# M1502X.net
KiCad netlist of a schematic drawn in EAGLE
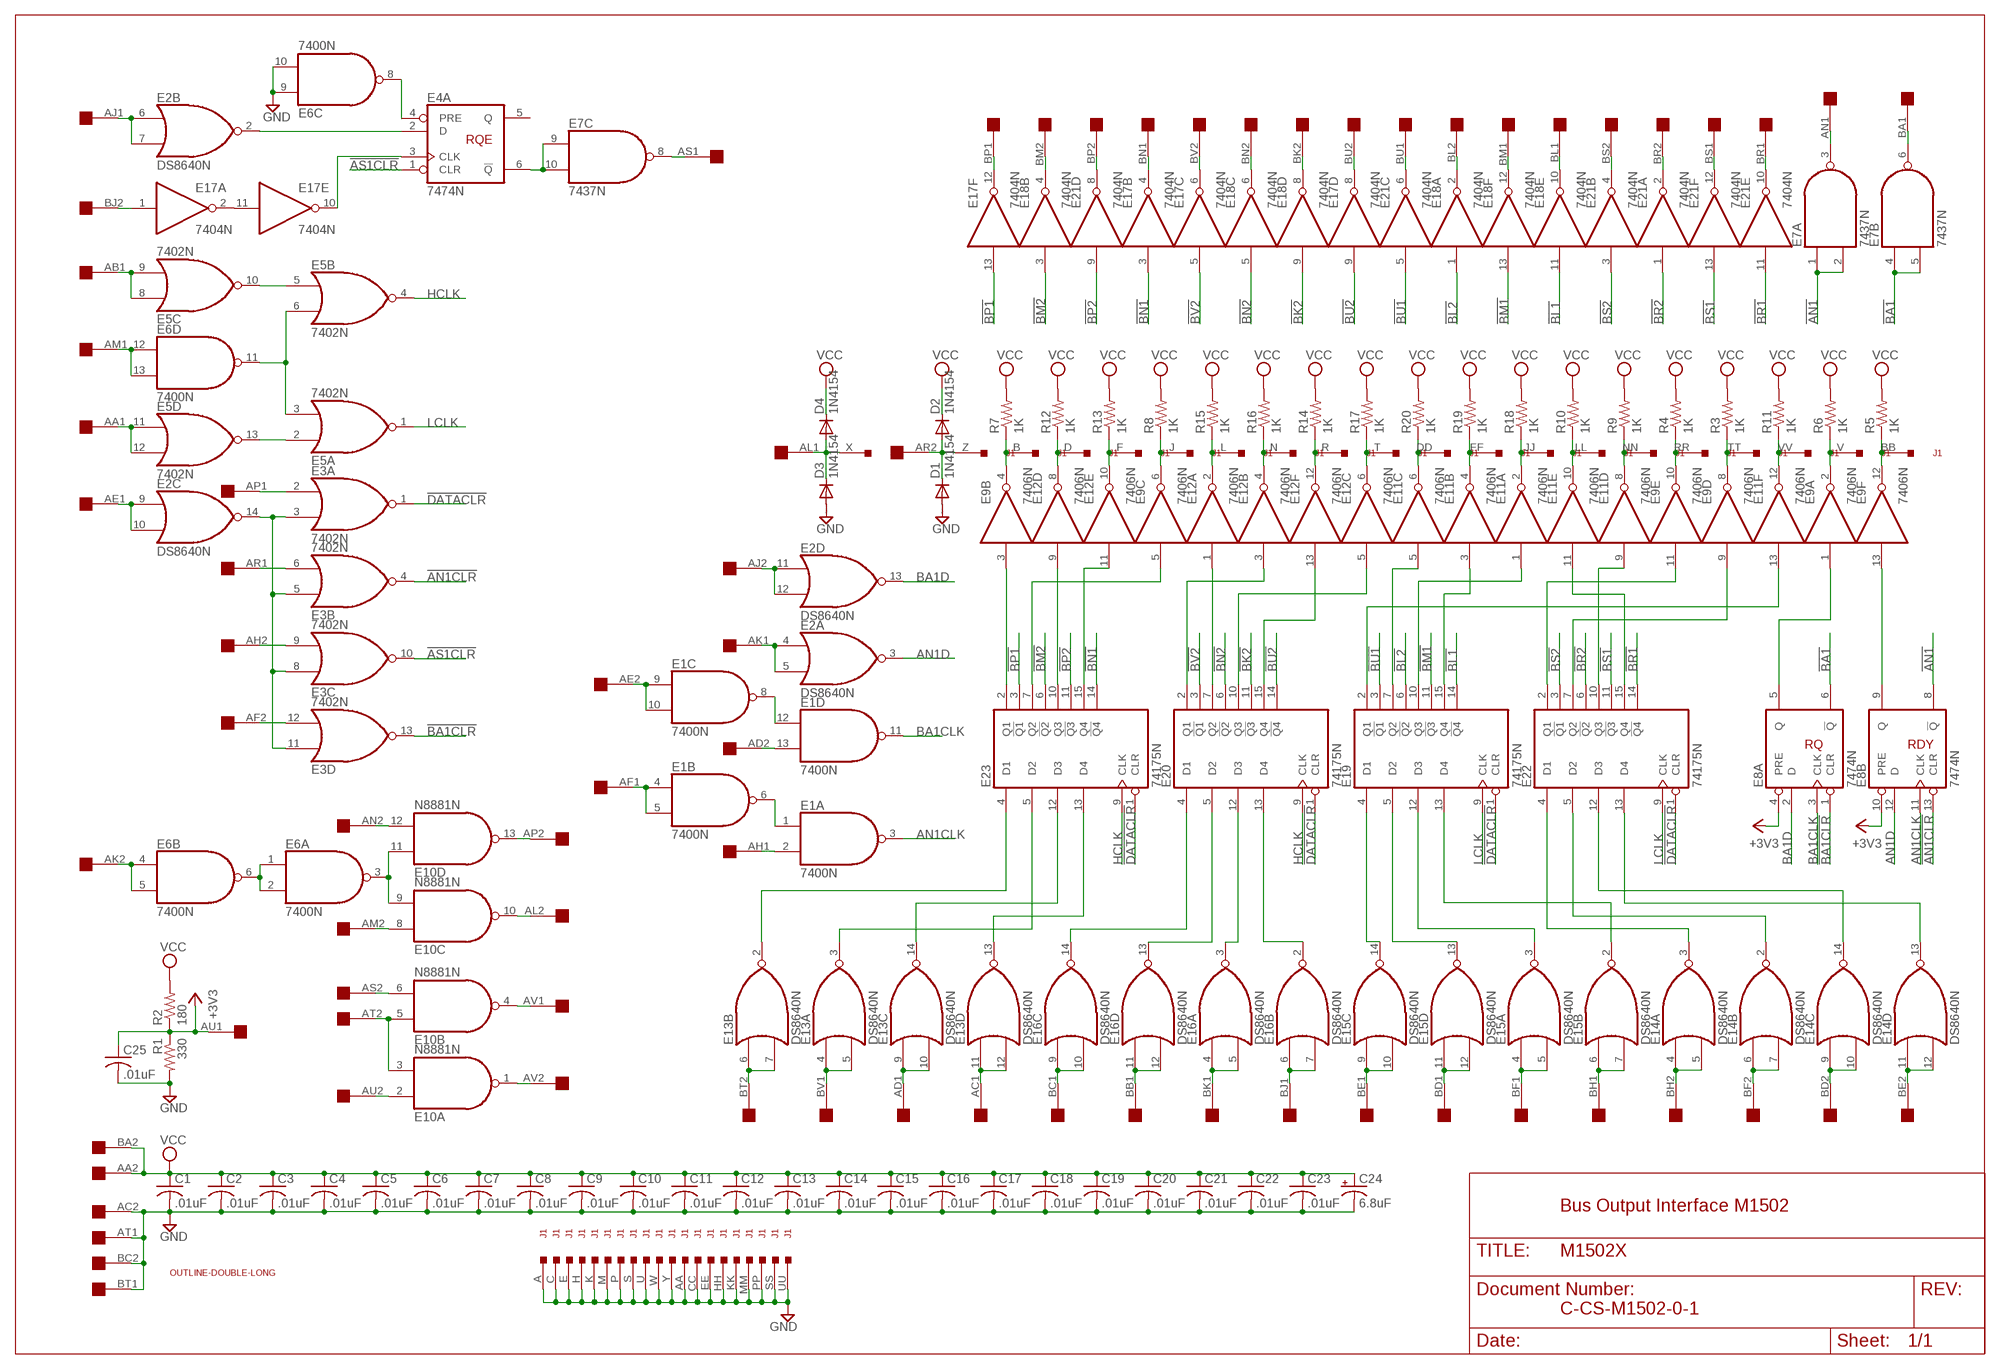
[diagram p0: schematic, sheet 1]

(export (version "E")
  (design (tool "Eeschema 10.0.6"))
  (components
    (comp (ref "C1")
      (value ".01uF")
      (footprint "eagle-import:C075-032X103")
      (libsource (lib "eagle-import") (part "C-US075-032X103"))
    )
    (comp (ref "C2")
      (value ".01uF")
      (footprint "eagle-import:C075-032X103")
      (libsource (lib "eagle-import") (part "C-US075-032X103"))
    )
    (comp (ref "C3")
      (value ".01uF")
      (footprint "eagle-import:C075-032X103")
      (libsource (lib "eagle-import") (part "C-US075-032X103"))
    )
    (comp (ref "C4")
      (value ".01uF")
      (footprint "eagle-import:C075-032X103")
      (libsource (lib "eagle-import") (part "C-US075-032X103"))
    )
    (comp (ref "C5")
      (value ".01uF")
      (footprint "eagle-import:C075-032X103")
      (libsource (lib "eagle-import") (part "C-US075-032X103"))
    )
    (comp (ref "C6")
      (value ".01uF")
      (footprint "eagle-import:C075-032X103")
      (libsource (lib "eagle-import") (part "C-US075-032X103"))
    )
    (comp (ref "C7")
      (value ".01uF")
      (footprint "eagle-import:C075-032X103")
      (libsource (lib "eagle-import") (part "C-US075-032X103"))
    )
    (comp (ref "C8")
      (value ".01uF")
      (footprint "eagle-import:C075-032X103")
      (libsource (lib "eagle-import") (part "C-US075-032X103"))
    )
    (comp (ref "C9")
      (value ".01uF")
      (footprint "eagle-import:C075-032X103")
      (libsource (lib "eagle-import") (part "C-US075-032X103"))
    )
    (comp (ref "C10")
      (value ".01uF")
      (footprint "eagle-import:C075-032X103")
      (libsource (lib "eagle-import") (part "C-US075-032X103"))
    )
    (comp (ref "C11")
      (value ".01uF")
      (footprint "eagle-import:C075-032X103")
      (libsource (lib "eagle-import") (part "C-US075-032X103"))
    )
    (comp (ref "C12")
      (value ".01uF")
      (footprint "eagle-import:C075-032X103")
      (libsource (lib "eagle-import") (part "C-US075-032X103"))
    )
    (comp (ref "C13")
      (value ".01uF")
      (footprint "eagle-import:C075-032X103")
      (libsource (lib "eagle-import") (part "C-US075-032X103"))
    )
    (comp (ref "C14")
      (value ".01uF")
      (footprint "eagle-import:C075-032X103")
      (libsource (lib "eagle-import") (part "C-US075-032X103"))
    )
    (comp (ref "C15")
      (value ".01uF")
      (footprint "eagle-import:C075-032X103")
      (libsource (lib "eagle-import") (part "C-US075-032X103"))
    )
    (comp (ref "C16")
      (value ".01uF")
      (footprint "eagle-import:C075-032X103")
      (libsource (lib "eagle-import") (part "C-US075-032X103"))
    )
    (comp (ref "C17")
      (value ".01uF")
      (footprint "eagle-import:C075-032X103")
      (libsource (lib "eagle-import") (part "C-US075-032X103"))
    )
    (comp (ref "C18")
      (value ".01uF")
      (footprint "eagle-import:C075-032X103")
      (libsource (lib "eagle-import") (part "C-US075-032X103"))
    )
    (comp (ref "C19")
      (value ".01uF")
      (footprint "eagle-import:C075-032X103")
      (libsource (lib "eagle-import") (part "C-US075-032X103"))
    )
    (comp (ref "C20")
      (value ".01uF")
      (footprint "eagle-import:C075-032X103")
      (libsource (lib "eagle-import") (part "C-US075-032X103"))
    )
    (comp (ref "C21")
      (value ".01uF")
      (footprint "eagle-import:C075-032X103")
      (libsource (lib "eagle-import") (part "C-US075-032X103"))
    )
    (comp (ref "C22")
      (value ".01uF")
      (footprint "eagle-import:C075-032X103")
      (libsource (lib "eagle-import") (part "C-US075-032X103"))
    )
    (comp (ref "C23")
      (value ".01uF")
      (footprint "eagle-import:C075-032X103")
      (libsource (lib "eagle-import") (part "C-US075-032X103"))
    )
    (comp (ref "C24")
      (value "6.8uF")
      (footprint "eagle-import:E12-8")
      (libsource (lib "eagle-import") (part "CPOL-USE20-8AXIAL"))
    )
    (comp (ref "C25")
      (value ".01uF")
      (footprint "eagle-import:C075-032X103")
      (libsource (lib "eagle-import") (part "C-US075-032X103"))
    )
    (comp (ref "D1")
      (value "1N4154")
      (footprint "eagle-import:DO35-10")
      (libsource (lib "eagle-import") (part "DIODE-DO35-10"))
    )
    (comp (ref "D2")
      (value "1N4154")
      (footprint "eagle-import:DO35-10")
      (libsource (lib "eagle-import") (part "DIODE-DO35-10"))
    )
    (comp (ref "D3")
      (value "1N4154")
      (footprint "eagle-import:DO35-10")
      (libsource (lib "eagle-import") (part "DIODE-DO35-10"))
    )
    (comp (ref "D4")
      (value "1N4154")
      (footprint "eagle-import:DO35-10")
      (libsource (lib "eagle-import") (part "DIODE-DO35-10"))
    )
    (comp (ref "E1")
      (value "7400N")
      (footprint "eagle-import:DIL14")
      (libsource (lib "eagle-import") (part "7400N"))
    )
    (comp (ref "E2")
      (value "DS8640N")
      (footprint "eagle-import:DIL14")
      (libsource (lib "eagle-import") (part "DS8640N"))
    )
    (comp (ref "E3")
      (value "7402N")
      (footprint "eagle-import:DIL14")
      (libsource (lib "eagle-import") (part "7402N"))
    )
    (comp (ref "E4")
      (value "7474N")
      (footprint "eagle-import:DIL14")
      (libsource (lib "eagle-import") (part "7474NS"))
    )
    (comp (ref "E5")
      (value "7402N")
      (footprint "eagle-import:DIL14")
      (libsource (lib "eagle-import") (part "7402N"))
    )
    (comp (ref "E6")
      (value "7400N")
      (footprint "eagle-import:DIL14")
      (libsource (lib "eagle-import") (part "7400N"))
    )
    (comp (ref "E7")
      (value "7437N")
      (footprint "eagle-import:DIL14")
      (libsource (lib "eagle-import") (part "7437N"))
    )
    (comp (ref "E8")
      (value "7474N")
      (footprint "eagle-import:DIL14")
      (libsource (lib "eagle-import") (part "7474NS"))
    )
    (comp (ref "E9")
      (value "7406N")
      (footprint "eagle-import:DIL14")
      (libsource (lib "eagle-import") (part "7406N"))
    )
    (comp (ref "E10")
      (value "N8881N")
      (footprint "eagle-import:DIL14")
      (libsource (lib "eagle-import") (part "N8881N"))
    )
    (comp (ref "E11")
      (value "7406N")
      (footprint "eagle-import:DIL14")
      (libsource (lib "eagle-import") (part "7406N"))
    )
    (comp (ref "E12")
      (value "7406N")
      (footprint "eagle-import:DIL14")
      (libsource (lib "eagle-import") (part "7406N"))
    )
    (comp (ref "E13")
      (value "DS8640N")
      (footprint "eagle-import:DIL14")
      (libsource (lib "eagle-import") (part "DS8640N"))
    )
    (comp (ref "E14")
      (value "DS8640N")
      (footprint "eagle-import:DIL14")
      (libsource (lib "eagle-import") (part "DS8640N"))
    )
    (comp (ref "E15")
      (value "DS8640N")
      (footprint "eagle-import:DIL14")
      (libsource (lib "eagle-import") (part "DS8640N"))
    )
    (comp (ref "E16")
      (value "DS8640N")
      (footprint "eagle-import:DIL14")
      (libsource (lib "eagle-import") (part "DS8640N"))
    )
    (comp (ref "E17")
      (value "7404N")
      (footprint "eagle-import:DIL14")
      (libsource (lib "eagle-import") (part "7404N"))
    )
    (comp (ref "E18")
      (value "7404N")
      (footprint "eagle-import:DIL14")
      (libsource (lib "eagle-import") (part "7404N"))
    )
    (comp (ref "E19")
      (value "74175N")
      (footprint "eagle-import:DIL16")
      (libsource (lib "eagle-import") (part "74175N"))
    )
    (comp (ref "E20")
      (value "74175N")
      (footprint "eagle-import:DIL16")
      (libsource (lib "eagle-import") (part "74175N"))
    )
    (comp (ref "E21")
      (value "7404N")
      (footprint "eagle-import:DIL14")
      (libsource (lib "eagle-import") (part "7404N"))
    )
    (comp (ref "E22")
      (value "74175N")
      (footprint "eagle-import:DIL16")
      (libsource (lib "eagle-import") (part "74175N"))
    )
    (comp (ref "E23")
      (value "74175N")
      (footprint "eagle-import:DIL16")
      (libsource (lib "eagle-import") (part "74175N"))
    )
    (comp (ref "J1")
      (value "DEC40PINSH")
      (footprint "eagle-import:DEC40PINH")
      (libsource (lib "eagle-import") (part "DEC40PINSH"))
    )
    (comp (ref "R1")
      (value "330")
      (footprint "eagle-import:0207_10")
      (libsource (lib "eagle-import") (part "R-US_0207/10"))
    )
    (comp (ref "R2")
      (value "180")
      (footprint "eagle-import:0207_10")
      (libsource (lib "eagle-import") (part "R-US_0207/10"))
    )
    (comp (ref "R3")
      (value "1K")
      (footprint "eagle-import:0207_10")
      (libsource (lib "eagle-import") (part "R-US_0207/10"))
    )
    (comp (ref "R4")
      (value "1K")
      (footprint "eagle-import:0207_10")
      (libsource (lib "eagle-import") (part "R-US_0207/10"))
    )
    (comp (ref "R5")
      (value "1K")
      (footprint "eagle-import:0207_10")
      (libsource (lib "eagle-import") (part "R-US_0207/10"))
    )
    (comp (ref "R6")
      (value "1K")
      (footprint "eagle-import:0207_10")
      (libsource (lib "eagle-import") (part "R-US_0207/10"))
    )
    (comp (ref "R7")
      (value "1K")
      (footprint "eagle-import:0207_10")
      (libsource (lib "eagle-import") (part "R-US_0207/10"))
    )
    (comp (ref "R8")
      (value "1K")
      (footprint "eagle-import:0207_10")
      (libsource (lib "eagle-import") (part "R-US_0207/10"))
    )
    (comp (ref "R9")
      (value "1K")
      (footprint "eagle-import:0207_10")
      (libsource (lib "eagle-import") (part "R-US_0207/10"))
    )
    (comp (ref "R10")
      (value "1K")
      (footprint "eagle-import:0207_10")
      (libsource (lib "eagle-import") (part "R-US_0207/10"))
    )
    (comp (ref "R11")
      (value "1K")
      (footprint "eagle-import:0207_10")
      (libsource (lib "eagle-import") (part "R-US_0207/10"))
    )
    (comp (ref "R12")
      (value "1K")
      (footprint "eagle-import:0207_10")
      (libsource (lib "eagle-import") (part "R-US_0207/10"))
    )
    (comp (ref "R13")
      (value "1K")
      (footprint "eagle-import:0207_10")
      (libsource (lib "eagle-import") (part "R-US_0207/10"))
    )
    (comp (ref "R14")
      (value "1K")
      (footprint "eagle-import:0207_10")
      (libsource (lib "eagle-import") (part "R-US_0207/10"))
    )
    (comp (ref "R15")
      (value "1K")
      (footprint "eagle-import:0207_10")
      (libsource (lib "eagle-import") (part "R-US_0207/10"))
    )
    (comp (ref "R16")
      (value "1K")
      (footprint "eagle-import:0207_10")
      (libsource (lib "eagle-import") (part "R-US_0207/10"))
    )
    (comp (ref "R17")
      (value "1K")
      (footprint "eagle-import:0207_10")
      (libsource (lib "eagle-import") (part "R-US_0207/10"))
    )
    (comp (ref "R18")
      (value "1K")
      (footprint "eagle-import:0207_10")
      (libsource (lib "eagle-import") (part "R-US_0207/10"))
    )
    (comp (ref "R19")
      (value "1K")
      (footprint "eagle-import:0207_10")
      (libsource (lib "eagle-import") (part "R-US_0207/10"))
    )
    (comp (ref "R20")
      (value "1K")
      (footprint "eagle-import:0207_10")
      (libsource (lib "eagle-import") (part "R-US_0207/10"))
    )
    (comp (ref "U$1")
      (value "OUTLINE-DOUBLE-LONG")
      (footprint "eagle-import:DOUBLE-LONG")
      (libsource (lib "eagle-import") (part "OUTLINE-DOUBLE-LONG"))
    )
    (comp (ref "U$3")
      (value "DOUBLE")
      (footprint "eagle-import:EDGE-CON4")
      (libsource (lib "eagle-import") (part "DOUBLE"))
    )
  )
  (nets
    (net (code "1") (name "+3V3") (class "Default")
      (node (ref "C25") (pin "1") (pinfunction "1_1") (pintype "passive"))
      (node (ref "E8") (pin "10") (pinfunction "PRE_10") (pintype "input"))
      (node (ref "E8") (pin "4") (pinfunction "PRE_4") (pintype "input"))
      (node (ref "R1") (pin "1") (pinfunction "1_1") (pintype "passive"))
      (node (ref "R2") (pin "1") (pinfunction "1_1") (pintype "passive"))
      (node (ref "U$3") (pin "AU1") (pinfunction "1_AU1") (pintype "bidirectional"))
    )
    (net (code "2") (name "/AN1CLK") (class "Default")
      (node (ref "E1") (pin "3") (pinfunction "O_3") (pintype "output"))
      (node (ref "E8") (pin "11") (pinfunction "CLK_11") (pintype "input"))
    )
    (net (code "3") (name "/AN1D") (class "Default")
      (node (ref "E2") (pin "3") (pinfunction "O_3") (pintype "output"))
      (node (ref "E8") (pin "12") (pinfunction "D_12") (pintype "input"))
    )
    (net (code "4") (name "/BA1CLK") (class "Default")
      (node (ref "E1") (pin "11") (pinfunction "O_11") (pintype "output"))
      (node (ref "E8") (pin "3") (pinfunction "CLK_3") (pintype "input"))
    )
    (net (code "5") (name "/BA1D") (class "Default")
      (node (ref "E2") (pin "13") (pinfunction "O_13") (pintype "output"))
      (node (ref "E8") (pin "2") (pinfunction "D_2") (pintype "input"))
    )
    (net (code "6") (name "/HCLK") (class "Default")
      (node (ref "E20") (pin "9") (pinfunction "CLK_9") (pintype "input"))
      (node (ref "E23") (pin "9") (pinfunction "CLK_9") (pintype "input"))
      (node (ref "E5") (pin "4") (pinfunction "O_4") (pintype "output"))
    )
    (net (code "7") (name "/LCLK") (class "Default")
      (node (ref "E19") (pin "9") (pinfunction "CLK_9") (pintype "input"))
      (node (ref "E22") (pin "9") (pinfunction "CLK_9") (pintype "input"))
      (node (ref "E5") (pin "1") (pinfunction "O_1") (pintype "output"))
    )
    (net (code "8") (name "/~{AN1CLR}") (class "Default")
      (node (ref "E3") (pin "4") (pinfunction "O_4") (pintype "output"))
      (node (ref "E8") (pin "13") (pinfunction "CLR_13") (pintype "input"))
    )
    (net (code "9") (name "/~{AN1}") (class "Default")
      (node (ref "E7") (pin "1") (pinfunction "I0_1") (pintype "input"))
      (node (ref "E7") (pin "2") (pinfunction "I1_2") (pintype "input"))
      (node (ref "E8") (pin "8") (pinfunction "~{Q}_8") (pintype "output"))
    )
    (net (code "10") (name "/~{AS1CLR}") (class "Default")
      (node (ref "E3") (pin "10") (pinfunction "O_10") (pintype "output"))
      (node (ref "E4") (pin "1") (pinfunction "CLR_1") (pintype "input"))
    )
    (net (code "11") (name "/~{BA1CLR}") (class "Default")
      (node (ref "E3") (pin "13") (pinfunction "O_13") (pintype "output"))
      (node (ref "E8") (pin "1") (pinfunction "CLR_1") (pintype "input"))
    )
    (net (code "12") (name "/~{BA1}") (class "Default")
      (node (ref "E7") (pin "4") (pinfunction "I0_4") (pintype "input"))
      (node (ref "E7") (pin "5") (pinfunction "I1_5") (pintype "input"))
      (node (ref "E8") (pin "6") (pinfunction "~{Q}_6") (pintype "output"))
    )
    (net (code "13") (name "/~{BK2}") (class "Default")
      (node (ref "E18") (pin "9") (pinfunction "I_9") (pintype "input"))
      (node (ref "E20") (pin "11") (pinfunction "~{Q3}_11") (pintype "output"))
    )
    (net (code "14") (name "/~{BL1}") (class "Default")
      (node (ref "E18") (pin "11") (pinfunction "I_11") (pintype "input"))
      (node (ref "E19") (pin "14") (pinfunction "~{Q4}_14") (pintype "output"))
    )
    (net (code "15") (name "/~{BL2}") (class "Default")
      (node (ref "E18") (pin "1") (pinfunction "I_1") (pintype "input"))
      (node (ref "E19") (pin "6") (pinfunction "~{Q2}_6") (pintype "output"))
    )
    (net (code "16") (name "/~{BM1}") (class "Default")
      (node (ref "E18") (pin "13") (pinfunction "I_13") (pintype "input"))
      (node (ref "E19") (pin "11") (pinfunction "~{Q3}_11") (pintype "output"))
    )
    (net (code "17") (name "/~{BM2}") (class "Default")
      (node (ref "E18") (pin "3") (pinfunction "I_3") (pintype "input"))
      (node (ref "E23") (pin "6") (pinfunction "~{Q2}_6") (pintype "output"))
    )
    (net (code "18") (name "/~{BN1}") (class "Default")
      (node (ref "E17") (pin "3") (pinfunction "I_3") (pintype "input"))
      (node (ref "E23") (pin "14") (pinfunction "~{Q4}_14") (pintype "output"))
    )
    (net (code "19") (name "/~{BN2}") (class "Default")
      (node (ref "E18") (pin "5") (pinfunction "I_5") (pintype "input"))
      (node (ref "E20") (pin "6") (pinfunction "~{Q2}_6") (pintype "output"))
    )
    (net (code "20") (name "/~{BP1}") (class "Default")
      (node (ref "E17") (pin "13") (pinfunction "I_13") (pintype "input"))
      (node (ref "E23") (pin "3") (pinfunction "~{Q1}_3") (pintype "output"))
    )
    (net (code "21") (name "/~{BP2}") (class "Default")
      (node (ref "E21") (pin "9") (pinfunction "I_9") (pintype "input"))
      (node (ref "E23") (pin "11") (pinfunction "~{Q3}_11") (pintype "output"))
    )
    (net (code "22") (name "/~{BR1}") (class "Default")
      (node (ref "E21") (pin "11") (pinfunction "I_11") (pintype "input"))
      (node (ref "E22") (pin "14") (pinfunction "~{Q4}_14") (pintype "output"))
    )
    (net (code "23") (name "/~{BR2}") (class "Default")
      (node (ref "E21") (pin "1") (pinfunction "I_1") (pintype "input"))
      (node (ref "E22") (pin "6") (pinfunction "~{Q2}_6") (pintype "output"))
    )
    (net (code "24") (name "/~{BS1}") (class "Default")
      (node (ref "E21") (pin "13") (pinfunction "I_13") (pintype "input"))
      (node (ref "E22") (pin "11") (pinfunction "~{Q3}_11") (pintype "output"))
    )
    (net (code "25") (name "/~{BS2}") (class "Default")
      (node (ref "E21") (pin "3") (pinfunction "I_3") (pintype "input"))
      (node (ref "E22") (pin "3") (pinfunction "~{Q1}_3") (pintype "output"))
    )
    (net (code "26") (name "/~{BU1}") (class "Default")
      (node (ref "E19") (pin "3") (pinfunction "~{Q1}_3") (pintype "output"))
      (node (ref "E21") (pin "5") (pinfunction "I_5") (pintype "input"))
    )
    (net (code "27") (name "/~{BU2}") (class "Default")
      (node (ref "E17") (pin "9") (pinfunction "I_9") (pintype "input"))
      (node (ref "E20") (pin "14") (pinfunction "~{Q4}_14") (pintype "output"))
    )
    (net (code "28") (name "/~{BV2}") (class "Default")
      (node (ref "E17") (pin "5") (pinfunction "I_5") (pintype "input"))
      (node (ref "E20") (pin "3") (pinfunction "~{Q1}_3") (pintype "output"))
    )
    (net (code "29") (name "/~{DATACLR}") (class "Default")
      (node (ref "E19") (pin "1") (pinfunction "CLR_1") (pintype "input"))
      (node (ref "E20") (pin "1") (pinfunction "CLR_1") (pintype "input"))
      (node (ref "E22") (pin "1") (pinfunction "CLR_1") (pintype "input"))
      (node (ref "E23") (pin "1") (pinfunction "CLR_1") (pintype "input"))
      (node (ref "E3") (pin "1") (pinfunction "O_1") (pintype "output"))
    )
    (net (code "30") (name "GND") (class "Default")
      (node (ref "C1") (pin "2") (pinfunction "2_2") (pintype "passive"))
      (node (ref "C10") (pin "2") (pinfunction "2_2") (pintype "passive"))
      (node (ref "C11") (pin "2") (pinfunction "2_2") (pintype "passive"))
      (node (ref "C12") (pin "2") (pinfunction "2_2") (pintype "passive"))
      (node (ref "C13") (pin "2") (pinfunction "2_2") (pintype "passive"))
      (node (ref "C14") (pin "2") (pinfunction "2_2") (pintype "passive"))
      (node (ref "C15") (pin "2") (pinfunction "2_2") (pintype "passive"))
      (node (ref "C16") (pin "2") (pinfunction "2_2") (pintype "passive"))
      (node (ref "C17") (pin "2") (pinfunction "2_2") (pintype "passive"))
      (node (ref "C18") (pin "2") (pinfunction "2_2") (pintype "passive"))
      (node (ref "C19") (pin "2") (pinfunction "2_2") (pintype "passive"))
      (node (ref "C2") (pin "2") (pinfunction "2_2") (pintype "passive"))
      (node (ref "C20") (pin "2") (pinfunction "2_2") (pintype "passive"))
      (node (ref "C21") (pin "2") (pinfunction "2_2") (pintype "passive"))
      (node (ref "C22") (pin "2") (pinfunction "2_2") (pintype "passive"))
      (node (ref "C23") (pin "2") (pinfunction "2_2") (pintype "passive"))
      (node (ref "C24") (pin "-") (pinfunction "-_-") (pintype "passive"))
      (node (ref "C25") (pin "2") (pinfunction "2_2") (pintype "passive"))
      (node (ref "C3") (pin "2") (pinfunction "2_2") (pintype "passive"))
      (node (ref "C4") (pin "2") (pinfunction "2_2") (pintype "passive"))
      (node (ref "C5") (pin "2") (pinfunction "2_2") (pintype "passive"))
      (node (ref "C6") (pin "2") (pinfunction "2_2") (pintype "passive"))
      (node (ref "C7") (pin "2") (pinfunction "2_2") (pintype "passive"))
      (node (ref "C8") (pin "2") (pinfunction "2_2") (pintype "passive"))
      (node (ref "C9") (pin "2") (pinfunction "2_2") (pintype "passive"))
      (node (ref "D1") (pin "A") (pinfunction "A_A") (pintype "passive"))
      (node (ref "D3") (pin "A") (pinfunction "A_A") (pintype "passive"))
      (node (ref "E6") (pin "10") (pinfunction "I1_10") (pintype "input"))
      (node (ref "E6") (pin "9") (pinfunction "I0_9") (pintype "input"))
      (node (ref "J1") (pin "A") (pinfunction "P$2_A") (pintype "passive"))
      (node (ref "J1") (pin "AA") (pinfunction "P$2_AA") (pintype "passive"))
      (node (ref "J1") (pin "C") (pinfunction "P$2_C") (pintype "passive"))
      (node (ref "J1") (pin "CC") (pinfunction "P$2_CC") (pintype "passive"))
      (node (ref "J1") (pin "E") (pinfunction "P$2_E") (pintype "passive"))
      (node (ref "J1") (pin "EE") (pinfunction "P$2_EE") (pintype "passive"))
      (node (ref "J1") (pin "H") (pinfunction "P$2_H") (pintype "passive"))
      (node (ref "J1") (pin "HH") (pinfunction "P$2_HH") (pintype "passive"))
      (node (ref "J1") (pin "K") (pinfunction "P$2_K") (pintype "passive"))
      (node (ref "J1") (pin "KK") (pinfunction "P$2_KK") (pintype "passive"))
      (node (ref "J1") (pin "M") (pinfunction "P$2_M") (pintype "passive"))
      (node (ref "J1") (pin "MM") (pinfunction "P$2_MM") (pintype "passive"))
      (node (ref "J1") (pin "P") (pinfunction "P$2_P") (pintype "passive"))
      (node (ref "J1") (pin "PP") (pinfunction "P$2_PP") (pintype "passive"))
      (node (ref "J1") (pin "S") (pinfunction "P$2_S") (pintype "passive"))
      (node (ref "J1") (pin "SS") (pinfunction "P$2_SS") (pintype "passive"))
      (node (ref "J1") (pin "U") (pinfunction "P$2_U") (pintype "passive"))
      (node (ref "J1") (pin "UU") (pinfunction "P$2_UU") (pintype "passive"))
      (node (ref "J1") (pin "W") (pinfunction "P$2_W") (pintype "passive"))
      (node (ref "J1") (pin "Y") (pinfunction "P$2_Y") (pintype "passive"))
      (node (ref "R1") (pin "2") (pinfunction "2_2") (pintype "passive"))
      (node (ref "U$3") (pin "AC2") (pinfunction "1_AC2") (pintype "bidirectional"))
      (node (ref "U$3") (pin "AT1") (pinfunction "1_AT1") (pintype "bidirectional"))
      (node (ref "U$3") (pin "BC2") (pinfunction "1_BC2") (pintype "bidirectional"))
      (node (ref "U$3") (pin "BT1") (pinfunction "1_BT1") (pintype "bidirectional"))
    )
    (net (code "31") (name "Net-(E1A-I0)") (class "Default")
      (node (ref "E1") (pin "1") (pinfunction "I0_1") (pintype "input"))
      (node (ref "E1") (pin "6") (pinfunction "O_6") (pintype "output"))
    )
    (net (code "32") (name "Net-(E1A-I1)") (class "Default")
      (node (ref "E1") (pin "2") (pinfunction "I1_2") (pintype "input"))
      (node (ref "U$3") (pin "AH1") (pinfunction "1_AH1") (pintype "bidirectional"))
    )
    (net (code "33") (name "Net-(E1B-I0)") (class "Default")
      (node (ref "E1") (pin "4") (pinfunction "I0_4") (pintype "input"))
      (node (ref "E1") (pin "5") (pinfunction "I1_5") (pintype "input"))
      (node (ref "U$3") (pin "AF1") (pinfunction "1_AF1") (pintype "bidirectional"))
    )
    (net (code "34") (name "Net-(E1C-I0)") (class "Default")
      (node (ref "E1") (pin "10") (pinfunction "I1_10") (pintype "input"))
      (node (ref "E1") (pin "9") (pinfunction "I0_9") (pintype "input"))
      (node (ref "U$3") (pin "AE2") (pinfunction "1_AE2") (pintype "bidirectional"))
    )
    (net (code "35") (name "Net-(E1C-O)") (class "Default")
      (node (ref "E1") (pin "12") (pinfunction "I0_12") (pintype "input"))
      (node (ref "E1") (pin "8") (pinfunction "O_8") (pintype "output"))
    )
    (net (code "36") (name "Net-(E1D-I1)") (class "Default")
      (node (ref "E1") (pin "13") (pinfunction "I1_13") (pintype "input"))
      (node (ref "U$3") (pin "AD2") (pinfunction "1_AD2") (pintype "bidirectional"))
    )
    (net (code "37") (name "Net-(E2A-I0)") (class "Default")
      (node (ref "E2") (pin "4") (pinfunction "I0_4") (pintype "input"))
      (node (ref "E2") (pin "5") (pinfunction "I1_5") (pintype "input"))
      (node (ref "U$3") (pin "AK1") (pinfunction "1_AK1") (pintype "bidirectional"))
    )
    (net (code "38") (name "Net-(E2B-I0)") (class "Default")
      (node (ref "E2") (pin "6") (pinfunction "I0_6") (pintype "input"))
      (node (ref "E2") (pin "7") (pinfunction "I1_7") (pintype "input"))
      (node (ref "U$3") (pin "AJ1") (pinfunction "1_AJ1") (pintype "bidirectional"))
    )
    (net (code "39") (name "Net-(E2B-O)") (class "Default")
      (node (ref "E2") (pin "2") (pinfunction "O_2") (pintype "output"))
      (node (ref "E4") (pin "2") (pinfunction "D_2") (pintype "input"))
    )
    (net (code "40") (name "Net-(E2C-I0)") (class "Default")
      (node (ref "E2") (pin "10") (pinfunction "I1_10") (pintype "input"))
      (node (ref "E2") (pin "9") (pinfunction "I0_9") (pintype "input"))
      (node (ref "U$3") (pin "AE1") (pinfunction "1_AE1") (pintype "bidirectional"))
    )
    (net (code "41") (name "Net-(E2C-O)") (class "Default")
      (node (ref "E2") (pin "14") (pinfunction "O_14") (pintype "output"))
      (node (ref "E3") (pin "11") (pinfunction "I0_11") (pintype "input"))
      (node (ref "E3") (pin "3") (pinfunction "I1_3") (pintype "input"))
      (node (ref "E3") (pin "5") (pinfunction "I0_5") (pintype "input"))
      (node (ref "E3") (pin "8") (pinfunction "I0_8") (pintype "input"))
    )
    (net (code "42") (name "Net-(E2D-I0)") (class "Default")
      (node (ref "E2") (pin "11") (pinfunction "I0_11") (pintype "input"))
      (node (ref "E2") (pin "12") (pinfunction "I1_12") (pintype "input"))
      (node (ref "U$3") (pin "AJ2") (pinfunction "1_AJ2") (pintype "bidirectional"))
    )
    (net (code "43") (name "Net-(E3A-I0)") (class "Default")
      (node (ref "E3") (pin "2") (pinfunction "I0_2") (pintype "input"))
      (node (ref "U$3") (pin "AP1") (pinfunction "1_AP1") (pintype "bidirectional"))
    )
    (net (code "44") (name "Net-(E3B-I1)") (class "Default")
      (node (ref "E3") (pin "6") (pinfunction "I1_6") (pintype "input"))
      (node (ref "U$3") (pin "AR1") (pinfunction "1_AR1") (pintype "bidirectional"))
    )
    (net (code "45") (name "Net-(E3C-I1)") (class "Default")
      (node (ref "E3") (pin "9") (pinfunction "I1_9") (pintype "input"))
      (node (ref "U$3") (pin "AH2") (pinfunction "1_AH2") (pintype "bidirectional"))
    )
    (net (code "46") (name "Net-(E3D-I1)") (class "Default")
      (node (ref "E3") (pin "12") (pinfunction "I1_12") (pintype "input"))
      (node (ref "U$3") (pin "AF2") (pinfunction "1_AF2") (pintype "bidirectional"))
    )
    (net (code "47") (name "Net-(E4A-PRE)") (class "Default")
      (node (ref "E4") (pin "4") (pinfunction "PRE_4") (pintype "input"))
      (node (ref "E6") (pin "8") (pinfunction "O_8") (pintype "output"))
    )
    (net (code "48") (name "Net-(E4A-~{Q})") (class "Default")
      (node (ref "E4") (pin "6") (pinfunction "~{Q}_6") (pintype "output"))
      (node (ref "E7") (pin "10") (pinfunction "I1_10") (pintype "input"))
      (node (ref "E7") (pin "9") (pinfunction "I0_9") (pintype "input"))
    )
    (net (code "49") (name "Net-(E5A-I0)") (class "Default")
      (node (ref "E5") (pin "13") (pinfunction "O_13") (pintype "output"))
      (node (ref "E5") (pin "2") (pinfunction "I0_2") (pintype "input"))
    )
    (net (code "50") (name "Net-(E5A-I1)") (class "Default")
      (node (ref "E5") (pin "3") (pinfunction "I1_3") (pintype "input"))
      (node (ref "E5") (pin "6") (pinfunction "I1_6") (pintype "input"))
      (node (ref "E6") (pin "11") (pinfunction "O_11") (pintype "output"))
    )
    (net (code "51") (name "Net-(E5B-I0)") (class "Default")
      (node (ref "E5") (pin "10") (pinfunction "O_10") (pintype "output"))
      (node (ref "E5") (pin "5") (pinfunction "I0_5") (pintype "input"))
    )
    (net (code "52") (name "Net-(E5C-I0)") (class "Default")
      (node (ref "E5") (pin "8") (pinfunction "I0_8") (pintype "input"))
      (node (ref "E5") (pin "9") (pinfunction "I1_9") (pintype "input"))
      (node (ref "U$3") (pin "AB1") (pinfunction "1_AB1") (pintype "bidirectional"))
    )
    (net (code "53") (name "Net-(E5D-I0)") (class "Default")
      (node (ref "E5") (pin "11") (pinfunction "I0_11") (pintype "input"))
      (node (ref "E5") (pin "12") (pinfunction "I1_12") (pintype "input"))
      (node (ref "U$3") (pin "AA1") (pinfunction "1_AA1") (pintype "bidirectional"))
    )
    (net (code "54") (name "Net-(E6A-I0)") (class "Default")
      (node (ref "E6") (pin "1") (pinfunction "I0_1") (pintype "input"))
      (node (ref "E6") (pin "2") (pinfunction "I1_2") (pintype "input"))
      (node (ref "E6") (pin "6") (pinfunction "O_6") (pintype "output"))
    )
    (net (code "55") (name "Net-(E6B-I0)") (class "Default")
      (node (ref "E6") (pin "4") (pinfunction "I0_4") (pintype "input"))
      (node (ref "E6") (pin "5") (pinfunction "I1_5") (pintype "input"))
      (node (ref "U$3") (pin "AK2") (pinfunction "1_AK2") (pintype "bidirectional"))
    )
    (net (code "56") (name "Net-(E6D-I0)") (class "Default")
      (node (ref "E6") (pin "12") (pinfunction "I0_12") (pintype "input"))
      (node (ref "E6") (pin "13") (pinfunction "I1_13") (pintype "input"))
      (node (ref "U$3") (pin "AM1") (pinfunction "1_AM1") (pintype "bidirectional"))
    )
    (net (code "57") (name "Net-(E7A-O)") (class "Default")
      (node (ref "E7") (pin "3") (pinfunction "O_3") (pintype "output"))
      (node (ref "U$3") (pin "AN1") (pinfunction "1_AN1") (pintype "bidirectional"))
    )
    (net (code "58") (name "Net-(E7B-O)") (class "Default")
      (node (ref "E7") (pin "6") (pinfunction "O_6") (pintype "output"))
      (node (ref "U$3") (pin "BA1") (pinfunction "1_BA1") (pintype "bidirectional"))
    )
    (net (code "59") (name "Net-(E7C-O)") (class "Default")
      (node (ref "E7") (pin "8") (pinfunction "O_8") (pintype "output"))
      (node (ref "U$3") (pin "AS1") (pinfunction "1_AS1") (pintype "bidirectional"))
    )
    (net (code "60") (name "Net-(E8A-Q)") (class "Default")
      (node (ref "E8") (pin "5") (pinfunction "Q_5") (pintype "output"))
      (node (ref "E9") (pin "1") (pinfunction "I_1") (pintype "input"))
    )
    (net (code "61") (name "Net-(E8B-Q)") (class "Default")
      (node (ref "E8") (pin "9") (pinfunction "Q_9") (pintype "output"))
      (node (ref "E9") (pin "13") (pinfunction "I_13") (pintype "input"))
    )
    (net (code "62") (name "Net-(E9A-O)") (class "Default")
      (node (ref "E9") (pin "2") (pinfunction "O_2") (pintype "open_collector"))
      (node (ref "J1") (pin "V") (pinfunction "P$2_V") (pintype "passive"))
      (node (ref "R6") (pin "1") (pinfunction "1_1") (pintype "passive"))
    )
    (net (code "63") (name "Net-(E9B-O)") (class "Default")
      (node (ref "E9") (pin "4") (pinfunction "O_4") (pintype "open_collector"))
      (node (ref "J1") (pin "B") (pinfunction "P$2_B") (pintype "passive"))
      (node (ref "R7") (pin "1") (pinfunction "1_1") (pintype "passive"))
    )
    (net (code "64") (name "Net-(E9C-O)") (class "Default")
      (node (ref "E9") (pin "6") (pinfunction "O_6") (pintype "open_collector"))
      (node (ref "J1") (pin "J") (pinfunction "P$2_J") (pintype "passive"))
      (node (ref "R8") (pin "1") (pinfunction "1_1") (pintype "passive"))
    )
    (net (code "65") (name "Net-(E9D-O)") (class "Default")
      (node (ref "E9") (pin "8") (pinfunction "O_8") (pintype "open_collector"))
      (node (ref "J1") (pin "TT") (pinfunction "P$2_TT") (pintype "passive"))
      (node (ref "R3") (pin "1") (pinfunction "1_1") (pintype "passive"))
    )
    (net (code "66") (name "Net-(E9E-O)") (class "Default")
      (node (ref "E9") (pin "10") (pinfunction "O_10") (pintype "open_collector"))
      (node (ref "J1") (pin "RR") (pinfunction "P$2_RR") (pintype "passive"))
      (node (ref "R4") (pin "1") (pinfunction "1_1") (pintype "passive"))
    )
    (net (code "67") (name "Net-(E9F-O)") (class "Default")
      (node (ref "E9") (pin "12") (pinfunction "O_12") (pintype "open_collector"))
      (node (ref "J1") (pin "BB") (pinfunction "P$2_BB") (pintype "passive"))
      (node (ref "R5") (pin "1") (pinfunction "1_1") (pintype "passive"))
    )
    (net (code "68") (name "Net-(E10A-I0)") (class "Default")
      (node (ref "E10") (pin "2") (pinfunction "I0_2") (pintype "input"))
      (node (ref "U$3") (pin "AU2") (pinfunction "1_AU2") (pintype "bidirectional"))
    )
    (net (code "69") (name "Net-(E10A-I1)") (class "Default")
      (node (ref "E10") (pin "3") (pinfunction "I1_3") (pintype "input"))
      (node (ref "E10") (pin "5") (pinfunction "I0_5") (pintype "input"))
      (node (ref "U$3") (pin "AT2") (pinfunction "1_AT2") (pintype "bidirectional"))
    )
    (net (code "70") (name "Net-(E10A-O)") (class "Default")
      (node (ref "E10") (pin "1") (pinfunction "O_1") (pintype "open_collector"))
      (node (ref "U$3") (pin "AV2") (pinfunction "1_AV2") (pintype "bidirectional"))
    )
    (net (code "71") (name "Net-(E10B-I1)") (class "Default")
      (node (ref "E10") (pin "6") (pinfunction "I1_6") (pintype "input"))
      (node (ref "U$3") (pin "AS2") (pinfunction "1_AS2") (pintype "bidirectional"))
    )
    (net (code "72") (name "Net-(E10B-O)") (class "Default")
      (node (ref "E10") (pin "4") (pinfunction "O_4") (pintype "open_collector"))
      (node (ref "U$3") (pin "AV1") (pinfunction "1_AV1") (pintype "bidirectional"))
    )
    (net (code "73") (name "Net-(E10C-I0)") (class "Default")
      (node (ref "E10") (pin "8") (pinfunction "I0_8") (pintype "input"))
      (node (ref "U$3") (pin "AM2") (pinfunction "1_AM2") (pintype "bidirectional"))
    )
    (net (code "74") (name "Net-(E10C-I1)") (class "Default")
      (node (ref "E10") (pin "11") (pinfunction "I0_11") (pintype "input"))
      (node (ref "E10") (pin "9") (pinfunction "I1_9") (pintype "input"))
      (node (ref "E6") (pin "3") (pinfunction "O_3") (pintype "output"))
    )
    (net (code "75") (name "Net-(E10C-O)") (class "Default")
      (node (ref "E10") (pin "10") (pinfunction "O_10") (pintype "open_collector"))
      (node (ref "U$3") (pin "AL2") (pinfunction "1_AL2") (pintype "bidirectional"))
    )
    (net (code "76") (name "Net-(E10D-I1)") (class "Default")
      (node (ref "E10") (pin "12") (pinfunction "I1_12") (pintype "input"))
      (node (ref "U$3") (pin "AN2") (pinfunction "1_AN2") (pintype "bidirectional"))
    )
    (net (code "77") (name "Net-(E10D-O)") (class "Default")
      (node (ref "E10") (pin "13") (pinfunction "O_13") (pintype "open_collector"))
      (node (ref "U$3") (pin "AP2") (pinfunction "1_AP2") (pintype "bidirectional"))
    )
    (net (code "78") (name "Net-(E11A-I)") (class "Default")
      (node (ref "E11") (pin "1") (pinfunction "I_1") (pintype "input"))
      (node (ref "E19") (pin "10") (pinfunction "Q3_10") (pintype "output"))
    )
    (net (code "79") (name "Net-(E11A-O)") (class "Default")
      (node (ref "E11") (pin "2") (pinfunction "O_2") (pintype "open_collector"))
      (node (ref "J1") (pin "JJ") (pinfunction "P$2_JJ") (pintype "passive"))
      (node (ref "R18") (pin "1") (pinfunction "1_1") (pintype "passive"))
    )
    (net (code "80") (name "Net-(E11B-I)") (class "Default")
      (node (ref "E11") (pin "3") (pinfunction "I_3") (pintype "input"))
      (node (ref "E19") (pin "15") (pinfunction "Q4_15") (pintype "output"))
    )
    (net (code "81") (name "Net-(E11B-O)") (class "Default")
      (node (ref "E11") (pin "4") (pinfunction "O_4") (pintype "open_collector"))
      (node (ref "J1") (pin "FF") (pinfunction "P$2_FF") (pintype "passive"))
      (node (ref "R19") (pin "1") (pinfunction "1_1") (pintype "passive"))
    )
    (net (code "82") (name "Net-(E11C-I)") (class "Default")
      (node (ref "E11") (pin "5") (pinfunction "I_5") (pintype "input"))
      (node (ref "E19") (pin "7") (pinfunction "Q2_7") (pintype "output"))
    )
    (net (code "83") (name "Net-(E11C-O)") (class "Default")
      (node (ref "E11") (pin "6") (pinfunction "O_6") (pintype "open_collector"))
      (node (ref "J1") (pin "DD") (pinfunction "P$2_DD") (pintype "passive"))
      (node (ref "R20") (pin "1") (pinfunction "1_1") (pintype "passive"))
    )
    (net (code "84") (name "Net-(E11D-I)") (class "Default")
      (node (ref "E11") (pin "9") (pinfunction "I_9") (pintype "input"))
      (node (ref "E22") (pin "10") (pinfunction "Q3_10") (pintype "output"))
    )
    (net (code "85") (name "Net-(E11D-O)") (class "Default")
      (node (ref "E11") (pin "8") (pinfunction "O_8") (pintype "open_collector"))
      (node (ref "J1") (pin "NN") (pinfunction "P$2_NN") (pintype "passive"))
      (node (ref "R9") (pin "1") (pinfunction "1_1") (pintype "passive"))
    )
    (net (code "86") (name "Net-(E11E-I)") (class "Default")
      (node (ref "E11") (pin "11") (pinfunction "I_11") (pintype "input"))
      (node (ref "E22") (pin "15") (pinfunction "Q4_15") (pintype "output"))
    )
    (net (code "87") (name "Net-(E11E-O)") (class "Default")
      (node (ref "E11") (pin "10") (pinfunction "O_10") (pintype "open_collector"))
      (node (ref "J1") (pin "LL") (pinfunction "P$2_LL") (pintype "passive"))
      (node (ref "R10") (pin "1") (pinfunction "1_1") (pintype "passive"))
    )
    (net (code "88") (name "Net-(E11F-I)") (class "Default")
      (node (ref "E11") (pin "13") (pinfunction "I_13") (pintype "input"))
      (node (ref "E19") (pin "2") (pinfunction "Q1_2") (pintype "output"))
    )
    (net (code "89") (name "Net-(E11F-O)") (class "Default")
      (node (ref "E11") (pin "12") (pinfunction "O_12") (pintype "open_collector"))
      (node (ref "J1") (pin "VV") (pinfunction "P$2_VV") (pintype "passive"))
      (node (ref "R11") (pin "1") (pinfunction "1_1") (pintype "passive"))
    )
    (net (code "90") (name "Net-(E12A-I)") (class "Default")
      (node (ref "E12") (pin "1") (pinfunction "I_1") (pintype "input"))
      (node (ref "E20") (pin "7") (pinfunction "Q2_7") (pintype "output"))
    )
    (net (code "91") (name "Net-(E12A-O)") (class "Default")
      (node (ref "E12") (pin "2") (pinfunction "O_2") (pintype "open_collector"))
      (node (ref "J1") (pin "L") (pinfunction "P$2_L") (pintype "passive"))
      (node (ref "R15") (pin "1") (pinfunction "1_1") (pintype "passive"))
    )
    (net (code "92") (name "Net-(E12B-I)") (class "Default")
      (node (ref "E12") (pin "3") (pinfunction "I_3") (pintype "input"))
      (node (ref "E20") (pin "2") (pinfunction "Q1_2") (pintype "output"))
    )
    (net (code "93") (name "Net-(E12B-O)") (class "Default")
      (node (ref "E12") (pin "4") (pinfunction "O_4") (pintype "open_collector"))
      (node (ref "J1") (pin "N") (pinfunction "P$2_N") (pintype "passive"))
      (node (ref "R16") (pin "1") (pinfunction "1_1") (pintype "passive"))
    )
    (net (code "94") (name "Net-(E12C-I)") (class "Default")
      (node (ref "E12") (pin "5") (pinfunction "I_5") (pintype "input"))
      (node (ref "E20") (pin "10") (pinfunction "Q3_10") (pintype "output"))
    )
    (net (code "95") (name "Net-(E12C-O)") (class "Default")
      (node (ref "E12") (pin "6") (pinfunction "O_6") (pintype "open_collector"))
      (node (ref "J1") (pin "T") (pinfunction "P$2_T") (pintype "passive"))
      (node (ref "R17") (pin "1") (pinfunction "1_1") (pintype "passive"))
    )
    (net (code "96") (name "Net-(E12D-I)") (class "Default")
      (node (ref "E12") (pin "9") (pinfunction "I_9") (pintype "input"))
      (node (ref "E23") (pin "10") (pinfunction "Q3_10") (pintype "output"))
    )
    (net (code "97") (name "Net-(E12D-O)") (class "Default")
      (node (ref "E12") (pin "8") (pinfunction "O_8") (pintype "open_collector"))
      (node (ref "J1") (pin "D") (pinfunction "P$2_D") (pintype "passive"))
      (node (ref "R12") (pin "1") (pinfunction "1_1") (pintype "passive"))
    )
    (net (code "98") (name "Net-(E12E-I)") (class "Default")
      (node (ref "E12") (pin "11") (pinfunction "I_11") (pintype "input"))
      (node (ref "E23") (pin "15") (pinfunction "Q4_15") (pintype "output"))
    )
    (net (code "99") (name "Net-(E12E-O)") (class "Default")
      (node (ref "E12") (pin "10") (pinfunction "O_10") (pintype "open_collector"))
      (node (ref "J1") (pin "F") (pinfunction "P$2_F") (pintype "passive"))
      (node (ref "R13") (pin "1") (pinfunction "1_1") (pintype "passive"))
    )
    (net (code "100") (name "Net-(E12F-I)") (class "Default")
      (node (ref "E12") (pin "13") (pinfunction "I_13") (pintype "input"))
      (node (ref "E20") (pin "15") (pinfunction "Q4_15") (pintype "output"))
    )
    (net (code "101") (name "Net-(E12F-O)") (class "Default")
      (node (ref "E12") (pin "12") (pinfunction "O_12") (pintype "open_collector"))
      (node (ref "J1") (pin "R") (pinfunction "P$2_R") (pintype "passive"))
      (node (ref "R14") (pin "1") (pinfunction "1_1") (pintype "passive"))
    )
    (net (code "102") (name "Net-(E13A-I0)") (class "Default")
      (node (ref "E13") (pin "4") (pinfunction "I0_4") (pintype "input"))
      (node (ref "E13") (pin "5") (pinfunction "I1_5") (pintype "input"))
      (node (ref "U$3") (pin "BV1") (pinfunction "1_BV1") (pintype "bidirectional"))
    )
    (net (code "103") (name "Net-(E13A-O)") (class "Default")
      (node (ref "E13") (pin "3") (pinfunction "O_3") (pintype "output"))
      (node (ref "E23") (pin "5") (pinfunction "D2_5") (pintype "input"))
    )
    (net (code "104") (name "Net-(E13B-I0)") (class "Default")
      (node (ref "E13") (pin "6") (pinfunction "I0_6") (pintype "input"))
      (node (ref "E13") (pin "7") (pinfunction "I1_7") (pintype "input"))
      (node (ref "U$3") (pin "BT2") (pinfunction "1_BT2") (pintype "bidirectional"))
    )
    (net (code "105") (name "Net-(E13B-O)") (class "Default")
      (node (ref "E13") (pin "2") (pinfunction "O_2") (pintype "output"))
      (node (ref "E23") (pin "4") (pinfunction "D1_4") (pintype "input"))
    )
    (net (code "106") (name "Net-(E13C-I0)") (class "Default")
      (node (ref "E13") (pin "10") (pinfunction "I1_10") (pintype "input"))
      (node (ref "E13") (pin "9") (pinfunction "I0_9") (pintype "input"))
      (node (ref "U$3") (pin "AD1") (pinfunction "1_AD1") (pintype "bidirectional"))
    )
    (net (code "107") (name "Net-(E13C-O)") (class "Default")
      (node (ref "E13") (pin "14") (pinfunction "O_14") (pintype "output"))
      (node (ref "E23") (pin "12") (pinfunction "D3_12") (pintype "input"))
    )
    (net (code "108") (name "Net-(E13D-I0)") (class "Default")
      (node (ref "E13") (pin "11") (pinfunction "I0_11") (pintype "input"))
      (node (ref "E13") (pin "12") (pinfunction "I1_12") (pintype "input"))
      (node (ref "U$3") (pin "AC1") (pinfunction "1_AC1") (pintype "bidirectional"))
    )
    (net (code "109") (name "Net-(E13D-O)") (class "Default")
      (node (ref "E13") (pin "13") (pinfunction "O_13") (pintype "output"))
      (node (ref "E23") (pin "13") (pinfunction "D4_13") (pintype "input"))
    )
    (net (code "110") (name "Net-(E14A-I0)") (class "Default")
      (node (ref "E14") (pin "4") (pinfunction "I0_4") (pintype "input"))
      (node (ref "E14") (pin "5") (pinfunction "I1_5") (pintype "input"))
      (node (ref "U$3") (pin "BH2") (pinfunction "1_BH2") (pintype "bidirectional"))
    )
    (net (code "111") (name "Net-(E14A-O)") (class "Default")
      (node (ref "E14") (pin "3") (pinfunction "O_3") (pintype "output"))
      (node (ref "E22") (pin "4") (pinfunction "D1_4") (pintype "input"))
    )
    (net (code "112") (name "Net-(E14B-I0)") (class "Default")
      (node (ref "E14") (pin "6") (pinfunction "I0_6") (pintype "input"))
      (node (ref "E14") (pin "7") (pinfunction "I1_7") (pintype "input"))
      (node (ref "U$3") (pin "BF2") (pinfunction "1_BF2") (pintype "bidirectional"))
    )
    (net (code "113") (name "Net-(E14B-O)") (class "Default")
      (node (ref "E14") (pin "2") (pinfunction "O_2") (pintype "output"))
      (node (ref "E22") (pin "5") (pinfunction "D2_5") (pintype "input"))
    )
    (net (code "114") (name "Net-(E14C-I0)") (class "Default")
      (node (ref "E14") (pin "10") (pinfunction "I1_10") (pintype "input"))
      (node (ref "E14") (pin "9") (pinfunction "I0_9") (pintype "input"))
      (node (ref "U$3") (pin "BD2") (pinfunction "1_BD2") (pintype "bidirectional"))
    )
    (net (code "115") (name "Net-(E14C-O)") (class "Default")
      (node (ref "E14") (pin "14") (pinfunction "O_14") (pintype "output"))
      (node (ref "E22") (pin "12") (pinfunction "D3_12") (pintype "input"))
    )
    (net (code "116") (name "Net-(E14D-I0)") (class "Default")
      (node (ref "E14") (pin "11") (pinfunction "I0_11") (pintype "input"))
      (node (ref "E14") (pin "12") (pinfunction "I1_12") (pintype "input"))
      (node (ref "U$3") (pin "BE2") (pinfunction "1_BE2") (pintype "bidirectional"))
    )
    (net (code "117") (name "Net-(E14D-O)") (class "Default")
      (node (ref "E14") (pin "13") (pinfunction "O_13") (pintype "output"))
      (node (ref "E22") (pin "13") (pinfunction "D4_13") (pintype "input"))
    )
    (net (code "118") (name "Net-(E15A-I0)") (class "Default")
      (node (ref "E15") (pin "4") (pinfunction "I0_4") (pintype "input"))
      (node (ref "E15") (pin "5") (pinfunction "I1_5") (pintype "input"))
      (node (ref "U$3") (pin "BF1") (pinfunction "1_BF1") (pintype "bidirectional"))
    )
    (net (code "119") (name "Net-(E15A-O)") (class "Default")
      (node (ref "E15") (pin "3") (pinfunction "O_3") (pintype "output"))
      (node (ref "E19") (pin "12") (pinfunction "D3_12") (pintype "input"))
    )
    (net (code "120") (name "Net-(E15B-I0)") (class "Default")
      (node (ref "E15") (pin "6") (pinfunction "I0_6") (pintype "input"))
      (node (ref "E15") (pin "7") (pinfunction "I1_7") (pintype "input"))
      (node (ref "U$3") (pin "BH1") (pinfunction "1_BH1") (pintype "bidirectional"))
    )
    (net (code "121") (name "Net-(E15B-O)") (class "Default")
      (node (ref "E15") (pin "2") (pinfunction "O_2") (pintype "output"))
      (node (ref "E19") (pin "13") (pinfunction "D4_13") (pintype "input"))
    )
    (net (code "122") (name "Net-(E15C-I0)") (class "Default")
      (node (ref "E15") (pin "10") (pinfunction "I1_10") (pintype "input"))
      (node (ref "E15") (pin "9") (pinfunction "I0_9") (pintype "input"))
      (node (ref "U$3") (pin "BE1") (pinfunction "1_BE1") (pintype "bidirectional"))
    )
    (net (code "123") (name "Net-(E15C-O)") (class "Default")
      (node (ref "E15") (pin "14") (pinfunction "O_14") (pintype "output"))
      (node (ref "E19") (pin "4") (pinfunction "D1_4") (pintype "input"))
    )
    (net (code "124") (name "Net-(E15D-I0)") (class "Default")
      (node (ref "E15") (pin "11") (pinfunction "I0_11") (pintype "input"))
      (node (ref "E15") (pin "12") (pinfunction "I1_12") (pintype "input"))
      (node (ref "U$3") (pin "BD1") (pinfunction "1_BD1") (pintype "bidirectional"))
    )
    (net (code "125") (name "Net-(E15D-O)") (class "Default")
      (node (ref "E15") (pin "13") (pinfunction "O_13") (pintype "output"))
      (node (ref "E19") (pin "5") (pinfunction "D2_5") (pintype "input"))
    )
    (net (code "126") (name "Net-(E16A-I0)") (class "Default")
      (node (ref "E16") (pin "4") (pinfunction "I0_4") (pintype "input"))
      (node (ref "E16") (pin "5") (pinfunction "I1_5") (pintype "input"))
      (node (ref "U$3") (pin "BK1") (pinfunction "1_BK1") (pintype "bidirectional"))
    )
    (net (code "127") (name "Net-(E16A-O)") (class "Default")
      (node (ref "E16") (pin "3") (pinfunction "O_3") (pintype "output"))
      (node (ref "E20") (pin "12") (pinfunction "D3_12") (pintype "input"))
    )
    (net (code "128") (name "Net-(E16B-I0)") (class "Default")
      (node (ref "E16") (pin "6") (pinfunction "I0_6") (pintype "input"))
      (node (ref "E16") (pin "7") (pinfunction "I1_7") (pintype "input"))
      (node (ref "U$3") (pin "BJ1") (pinfunction "1_BJ1") (pintype "bidirectional"))
    )
    (net (code "129") (name "Net-(E16B-O)") (class "Default")
      (node (ref "E16") (pin "2") (pinfunction "O_2") (pintype "output"))
      (node (ref "E20") (pin "13") (pinfunction "D4_13") (pintype "input"))
    )
    (net (code "130") (name "Net-(E16C-I0)") (class "Default")
      (node (ref "E16") (pin "10") (pinfunction "I1_10") (pintype "input"))
      (node (ref "E16") (pin "9") (pinfunction "I0_9") (pintype "input"))
      (node (ref "U$3") (pin "BC1") (pinfunction "1_BC1") (pintype "bidirectional"))
    )
    (net (code "131") (name "Net-(E16C-O)") (class "Default")
      (node (ref "E16") (pin "14") (pinfunction "O_14") (pintype "output"))
      (node (ref "E20") (pin "4") (pinfunction "D1_4") (pintype "input"))
    )
    (net (code "132") (name "Net-(E16D-I0)") (class "Default")
      (node (ref "E16") (pin "11") (pinfunction "I0_11") (pintype "input"))
      (node (ref "E16") (pin "12") (pinfunction "I1_12") (pintype "input"))
      (node (ref "U$3") (pin "BB1") (pinfunction "1_BB1") (pintype "bidirectional"))
    )
    (net (code "133") (name "Net-(E16D-O)") (class "Default")
      (node (ref "E16") (pin "13") (pinfunction "O_13") (pintype "output"))
      (node (ref "E20") (pin "5") (pinfunction "D2_5") (pintype "input"))
    )
    (net (code "134") (name "Net-(E17A-I)") (class "Default")
      (node (ref "E17") (pin "1") (pinfunction "I_1") (pintype "input"))
      (node (ref "U$3") (pin "BJ2") (pinfunction "1_BJ2") (pintype "bidirectional"))
    )
    (net (code "135") (name "Net-(E17A-O)") (class "Default")
      (node (ref "E17") (pin "11") (pinfunction "I_11") (pintype "input"))
      (node (ref "E17") (pin "2") (pinfunction "O_2") (pintype "output"))
    )
    (net (code "136") (name "Net-(E17B-O)") (class "Default")
      (node (ref "E17") (pin "4") (pinfunction "O_4") (pintype "output"))
      (node (ref "U$3") (pin "BN1") (pinfunction "1_BN1") (pintype "bidirectional"))
    )
    (net (code "137") (name "Net-(E17C-O)") (class "Default")
      (node (ref "E17") (pin "6") (pinfunction "O_6") (pintype "output"))
      (node (ref "U$3") (pin "BV2") (pinfunction "1_BV2") (pintype "bidirectional"))
    )
    (net (code "138") (name "Net-(E17D-O)") (class "Default")
      (node (ref "E17") (pin "8") (pinfunction "O_8") (pintype "output"))
      (node (ref "U$3") (pin "BU2") (pinfunction "1_BU2") (pintype "bidirectional"))
    )
    (net (code "139") (name "Net-(E17E-O)") (class "Default")
      (node (ref "E17") (pin "10") (pinfunction "O_10") (pintype "output"))
      (node (ref "E4") (pin "3") (pinfunction "CLK_3") (pintype "input"))
    )
    (net (code "140") (name "Net-(E17F-O)") (class "Default")
      (node (ref "E17") (pin "12") (pinfunction "O_12") (pintype "output"))
      (node (ref "U$3") (pin "BP1") (pinfunction "1_BP1") (pintype "bidirectional"))
    )
    (net (code "141") (name "Net-(E18A-O)") (class "Default")
      (node (ref "E18") (pin "2") (pinfunction "O_2") (pintype "output"))
      (node (ref "U$3") (pin "BL2") (pinfunction "1_BL2") (pintype "bidirectional"))
    )
    (net (code "142") (name "Net-(E18B-O)") (class "Default")
      (node (ref "E18") (pin "4") (pinfunction "O_4") (pintype "output"))
      (node (ref "U$3") (pin "BM2") (pinfunction "1_BM2") (pintype "bidirectional"))
    )
    (net (code "143") (name "Net-(E18C-O)") (class "Default")
      (node (ref "E18") (pin "6") (pinfunction "O_6") (pintype "output"))
      (node (ref "U$3") (pin "BN2") (pinfunction "1_BN2") (pintype "bidirectional"))
    )
    (net (code "144") (name "Net-(E18D-O)") (class "Default")
      (node (ref "E18") (pin "8") (pinfunction "O_8") (pintype "output"))
      (node (ref "U$3") (pin "BK2") (pinfunction "1_BK2") (pintype "bidirectional"))
    )
    (net (code "145") (name "Net-(E18E-O)") (class "Default")
      (node (ref "E18") (pin "10") (pinfunction "O_10") (pintype "output"))
      (node (ref "U$3") (pin "BL1") (pinfunction "1_BL1") (pintype "bidirectional"))
    )
    (net (code "146") (name "Net-(E18F-O)") (class "Default")
      (node (ref "E18") (pin "12") (pinfunction "O_12") (pintype "output"))
      (node (ref "U$3") (pin "BM1") (pinfunction "1_BM1") (pintype "bidirectional"))
    )
    (net (code "147") (name "Net-(E21A-O)") (class "Default")
      (node (ref "E21") (pin "2") (pinfunction "O_2") (pintype "output"))
      (node (ref "U$3") (pin "BR2") (pinfunction "1_BR2") (pintype "bidirectional"))
    )
    (net (code "148") (name "Net-(E21B-O)") (class "Default")
      (node (ref "E21") (pin "4") (pinfunction "O_4") (pintype "output"))
      (node (ref "U$3") (pin "BS2") (pinfunction "1_BS2") (pintype "bidirectional"))
    )
    (net (code "149") (name "Net-(E21C-O)") (class "Default")
      (node (ref "E21") (pin "6") (pinfunction "O_6") (pintype "output"))
      (node (ref "U$3") (pin "BU1") (pinfunction "1_BU1") (pintype "bidirectional"))
    )
    (net (code "150") (name "Net-(E21D-O)") (class "Default")
      (node (ref "E21") (pin "8") (pinfunction "O_8") (pintype "output"))
      (node (ref "U$3") (pin "BP2") (pinfunction "1_BP2") (pintype "bidirectional"))
    )
    (net (code "151") (name "Net-(E21E-O)") (class "Default")
      (node (ref "E21") (pin "10") (pinfunction "O_10") (pintype "output"))
      (node (ref "U$3") (pin "BR1") (pinfunction "1_BR1") (pintype "bidirectional"))
    )
    (net (code "152") (name "Net-(E21F-O)") (class "Default")
      (node (ref "E21") (pin "12") (pinfunction "O_12") (pintype "output"))
      (node (ref "U$3") (pin "BS1") (pinfunction "1_BS1") (pintype "bidirectional"))
    )
    (net (code "153") (name "Net-(E22A-Q1)") (class "Default")
      (node (ref "E22") (pin "2") (pinfunction "Q1_2") (pintype "output"))
      (node (ref "E9") (pin "11") (pinfunction "I_11") (pintype "input"))
    )
    (net (code "154") (name "Net-(E22A-Q2)") (class "Default")
      (node (ref "E22") (pin "7") (pinfunction "Q2_7") (pintype "output"))
      (node (ref "E9") (pin "9") (pinfunction "I_9") (pintype "input"))
    )
    (net (code "155") (name "Net-(E23A-Q1)") (class "Default")
      (node (ref "E23") (pin "2") (pinfunction "Q1_2") (pintype "output"))
      (node (ref "E9") (pin "3") (pinfunction "I_3") (pintype "input"))
    )
    (net (code "156") (name "Net-(E23A-Q2)") (class "Default")
      (node (ref "E23") (pin "7") (pinfunction "Q2_7") (pintype "output"))
      (node (ref "E9") (pin "5") (pinfunction "I_5") (pintype "input"))
    )
    (net (code "157") (name "Net-(J1M-P$2)") (class "Default")
      (node (ref "D3") (pin "C") (pinfunction "C_C") (pintype "passive"))
      (node (ref "D4") (pin "A") (pinfunction "A_A") (pintype "passive"))
      (node (ref "J1") (pin "X") (pinfunction "P$2_X") (pintype "passive"))
      (node (ref "U$3") (pin "AL1") (pinfunction "1_AL1") (pintype "bidirectional"))
    )
    (net (code "158") (name "Net-(J1O-P$2)") (class "Default")
      (node (ref "D1") (pin "C") (pinfunction "C_C") (pintype "passive"))
      (node (ref "D2") (pin "A") (pinfunction "A_A") (pintype "passive"))
      (node (ref "J1") (pin "Z") (pinfunction "P$2_Z") (pintype "passive"))
      (node (ref "U$3") (pin "AR2") (pinfunction "1_AR2") (pintype "bidirectional"))
    )
    (net (code "159") (name "VCC") (class "Default")
      (node (ref "C1") (pin "1") (pinfunction "1_1") (pintype "passive"))
      (node (ref "C10") (pin "1") (pinfunction "1_1") (pintype "passive"))
      (node (ref "C11") (pin "1") (pinfunction "1_1") (pintype "passive"))
      (node (ref "C12") (pin "1") (pinfunction "1_1") (pintype "passive"))
      (node (ref "C13") (pin "1") (pinfunction "1_1") (pintype "passive"))
      (node (ref "C14") (pin "1") (pinfunction "1_1") (pintype "passive"))
      (node (ref "C15") (pin "1") (pinfunction "1_1") (pintype "passive"))
      (node (ref "C16") (pin "1") (pinfunction "1_1") (pintype "passive"))
      (node (ref "C17") (pin "1") (pinfunction "1_1") (pintype "passive"))
      (node (ref "C18") (pin "1") (pinfunction "1_1") (pintype "passive"))
      (node (ref "C19") (pin "1") (pinfunction "1_1") (pintype "passive"))
      (node (ref "C2") (pin "1") (pinfunction "1_1") (pintype "passive"))
      (node (ref "C20") (pin "1") (pinfunction "1_1") (pintype "passive"))
      (node (ref "C21") (pin "1") (pinfunction "1_1") (pintype "passive"))
      (node (ref "C22") (pin "1") (pinfunction "1_1") (pintype "passive"))
      (node (ref "C23") (pin "1") (pinfunction "1_1") (pintype "passive"))
      (node (ref "C24") (pin "+") (pinfunction "+_+") (pintype "passive"))
      (node (ref "C3") (pin "1") (pinfunction "1_1") (pintype "passive"))
      (node (ref "C4") (pin "1") (pinfunction "1_1") (pintype "passive"))
      (node (ref "C5") (pin "1") (pinfunction "1_1") (pintype "passive"))
      (node (ref "C6") (pin "1") (pinfunction "1_1") (pintype "passive"))
      (node (ref "C7") (pin "1") (pinfunction "1_1") (pintype "passive"))
      (node (ref "C8") (pin "1") (pinfunction "1_1") (pintype "passive"))
      (node (ref "C9") (pin "1") (pinfunction "1_1") (pintype "passive"))
      (node (ref "D2") (pin "C") (pinfunction "C_C") (pintype "passive"))
      (node (ref "D4") (pin "C") (pinfunction "C_C") (pintype "passive"))
      (node (ref "R10") (pin "2") (pinfunction "2_2") (pintype "passive"))
      (node (ref "R11") (pin "2") (pinfunction "2_2") (pintype "passive"))
      (node (ref "R12") (pin "2") (pinfunction "2_2") (pintype "passive"))
      (node (ref "R13") (pin "2") (pinfunction "2_2") (pintype "passive"))
      (node (ref "R14") (pin "2") (pinfunction "2_2") (pintype "passive"))
      (node (ref "R15") (pin "2") (pinfunction "2_2") (pintype "passive"))
      (node (ref "R16") (pin "2") (pinfunction "2_2") (pintype "passive"))
      (node (ref "R17") (pin "2") (pinfunction "2_2") (pintype "passive"))
      (node (ref "R18") (pin "2") (pinfunction "2_2") (pintype "passive"))
      (node (ref "R19") (pin "2") (pinfunction "2_2") (pintype "passive"))
      (node (ref "R2") (pin "2") (pinfunction "2_2") (pintype "passive"))
      (node (ref "R20") (pin "2") (pinfunction "2_2") (pintype "passive"))
      (node (ref "R3") (pin "2") (pinfunction "2_2") (pintype "passive"))
      (node (ref "R4") (pin "2") (pinfunction "2_2") (pintype "passive"))
      (node (ref "R5") (pin "2") (pinfunction "2_2") (pintype "passive"))
      (node (ref "R6") (pin "2") (pinfunction "2_2") (pintype "passive"))
      (node (ref "R7") (pin "2") (pinfunction "2_2") (pintype "passive"))
      (node (ref "R8") (pin "2") (pinfunction "2_2") (pintype "passive"))
      (node (ref "R9") (pin "2") (pinfunction "2_2") (pintype "passive"))
      (node (ref "U$3") (pin "AA2") (pinfunction "1_AA2") (pintype "bidirectional"))
      (node (ref "U$3") (pin "BA2") (pinfunction "1_BA2") (pintype "bidirectional"))
    )
    (net (code "160") (name "unconnected-(E4A-Q-Pad5)") (class "Default")
      (node (ref "E4") (pin "5") (pinfunction "Q_5") (pintype "output"))
    )
  )
)
